# rc_switch_dualsided_with_fet_driver.net
KiCad netlist of a schematic drawn in EAGLE
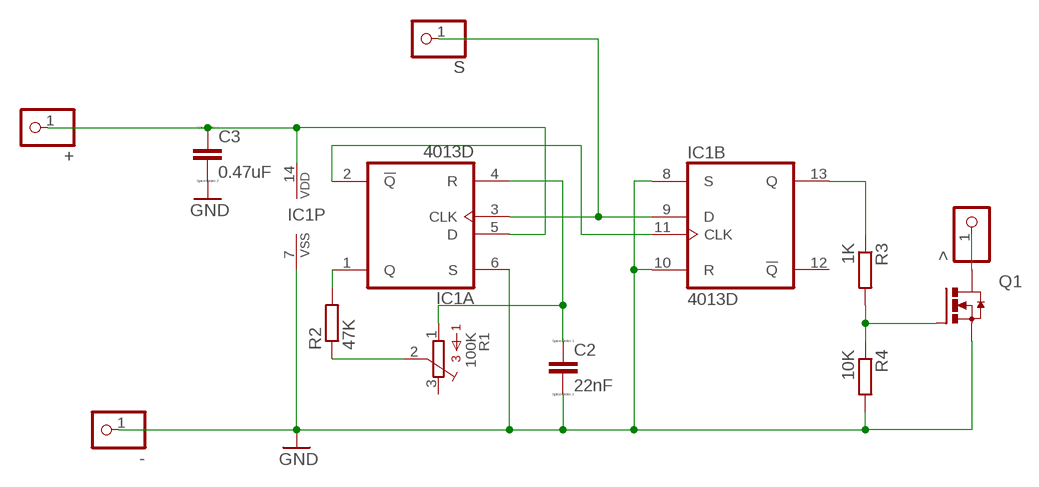
[diagram p0: schematic, sheet 1]

(export (version "E")
  (design (tool "Eeschema 10.0.6"))
  (components
    (comp (ref "+")
      (value "PINHD-1X1")
      (footprint "eagle-import:1X01")
      (libsource (lib "eagle-import") (part "PINHD-1X1"))
    )
    (comp (ref "-")
      (value "PINHD-1X1")
      (footprint "eagle-import:1X01")
      (libsource (lib "eagle-import") (part "PINHD-1X1"))
    )
    (comp (ref ">")
      (value "PINHD-1X1")
      (footprint "eagle-import:1X01")
      (libsource (lib "eagle-import") (part "PINHD-1X1"))
    )
    (comp (ref "C2")
      (value "22nF")
      (footprint "eagle-import:C3216")
      (libsource (lib "eagle-import") (part "CC3216"))
    )
    (comp (ref "C3")
      (value "0.47uF")
      (footprint "eagle-import:C3216")
      (libsource (lib "eagle-import") (part "CC3216"))
    )
    (comp (ref "IC1")
      (value "4013D")
      (footprint "eagle-import:SO14")
      (libsource (lib "eagle-import") (part "4013D"))
    )
    (comp (ref "Q1")
      (value "IRF3704S")
      (footprint "eagle-import:D2PACK")
      (libsource (lib "eagle-import") (part "IRF3704S"))
    )
    (comp (ref "R1")
      (value "100K")
      (footprint "eagle-import:3386P")
      (libsource (lib "eagle-import") (part "3386-P"))
    )
    (comp (ref "R2")
      (value "47K")
      (footprint "eagle-import:R3225")
      (libsource (lib "eagle-import") (part "R-EU_R3225"))
    )
    (comp (ref "R3")
      (value "1K")
      (footprint "eagle-import:R3225")
      (libsource (lib "eagle-import") (part "R-EU_R3225"))
    )
    (comp (ref "R4")
      (value "10K")
      (footprint "eagle-import:R3225")
      (libsource (lib "eagle-import") (part "R-EU_R3225"))
    )
    (comp (ref "S")
      (value "PINHD-1X1")
      (footprint "eagle-import:1X01")
      (libsource (lib "eagle-import") (part "PINHD-1X1"))
    )
  )
  (nets
    (net (code "1") (name "GND") (class "Default")
      (node (ref "-") (pin "1") (pinfunction "1_1") (pintype "passive"))
      (node (ref "C2") (pin "2") (pinfunction "2_2") (pintype "passive"))
      (node (ref "C3") (pin "2") (pinfunction "2_2") (pintype "passive"))
      (node (ref "IC1") (pin "10") (pinfunction "R_10") (pintype "input"))
      (node (ref "IC1") (pin "6") (pinfunction "S_6") (pintype "input"))
      (node (ref "IC1") (pin "7") (pinfunction "VSS_7") (pintype "power_in"))
      (node (ref "IC1") (pin "8") (pinfunction "S_8") (pintype "input"))
      (node (ref "Q1") (pin "3") (pinfunction "S_3") (pintype "passive"))
      (node (ref "R4") (pin "2") (pinfunction "2_2") (pintype "passive"))
    )
    (net (code "2") (name "Net-(IC1A-CLK)") (class "Default")
      (node (ref "IC1") (pin "3") (pinfunction "CLK_3") (pintype "input"))
      (node (ref "IC1") (pin "9") (pinfunction "D_9") (pintype "input"))
      (node (ref "S") (pin "1") (pinfunction "1_1") (pintype "passive"))
    )
    (net (code "3") (name "Net-(IC1A-D)") (class "Default")
      (node (ref "+") (pin "1") (pinfunction "1_1") (pintype "passive"))
      (node (ref "C3") (pin "1") (pinfunction "1_1") (pintype "passive"))
      (node (ref "IC1") (pin "14") (pinfunction "VDD_14") (pintype "power_in"))
      (node (ref "IC1") (pin "5") (pinfunction "D_5") (pintype "input"))
    )
    (net (code "4") (name "Net-(IC1A-Q)") (class "Default")
      (node (ref "IC1") (pin "1") (pinfunction "Q_1") (pintype "output"))
      (node (ref "R2") (pin "2") (pinfunction "2_2") (pintype "passive"))
    )
    (net (code "5") (name "Net-(IC1A-R)") (class "Default")
      (node (ref "C2") (pin "1") (pinfunction "1_1") (pintype "passive"))
      (node (ref "IC1") (pin "4") (pinfunction "R_4") (pintype "input"))
      (node (ref "R1") (pin "1") (pinfunction "1_1") (pintype "passive"))
    )
    (net (code "6") (name "Net-(IC1A-~{Q})") (class "Default")
      (node (ref "IC1") (pin "11") (pinfunction "CLK_11") (pintype "input"))
      (node (ref "IC1") (pin "2") (pinfunction "~{Q}_2") (pintype "output"))
    )
    (net (code "7") (name "Net-(IC1B-Q)") (class "Default")
      (node (ref "IC1") (pin "13") (pinfunction "Q_13") (pintype "output"))
      (node (ref "R3") (pin "1") (pinfunction "1_1") (pintype "passive"))
    )
    (net (code "8") (name "Net-(Q1-D)") (class "Default")
      (node (ref ">") (pin "1") (pinfunction "1_1") (pintype "passive"))
      (node (ref "Q1") (pin "2") (pinfunction "D_2") (pintype "passive"))
    )
    (net (code "9") (name "Net-(Q1-G)") (class "Default")
      (node (ref "Q1") (pin "1") (pinfunction "G_1") (pintype "passive"))
      (node (ref "R3") (pin "2") (pinfunction "2_2") (pintype "passive"))
      (node (ref "R4") (pin "1") (pinfunction "1_1") (pintype "passive"))
    )
    (net (code "10") (name "Net-(R1-Pad2)") (class "Default")
      (node (ref "R1") (pin "2") (pinfunction "2_2") (pintype "passive"))
      (node (ref "R2") (pin "1") (pinfunction "1_1") (pintype "passive"))
    )
    (net (code "11") (name "unconnected-(IC1B-~{Q}-Pad12)") (class "Default")
      (node (ref "IC1") (pin "12") (pinfunction "~{Q}_12") (pintype "output"))
    )
    (net (code "12") (name "unconnected-(R1-Pad3)") (class "Default")
      (node (ref "R1") (pin "3") (pinfunction "3_3") (pintype "passive"))
    )
  )
)
